# micropeak.net
KiCad netlist of a schematic drawn in EAGLE
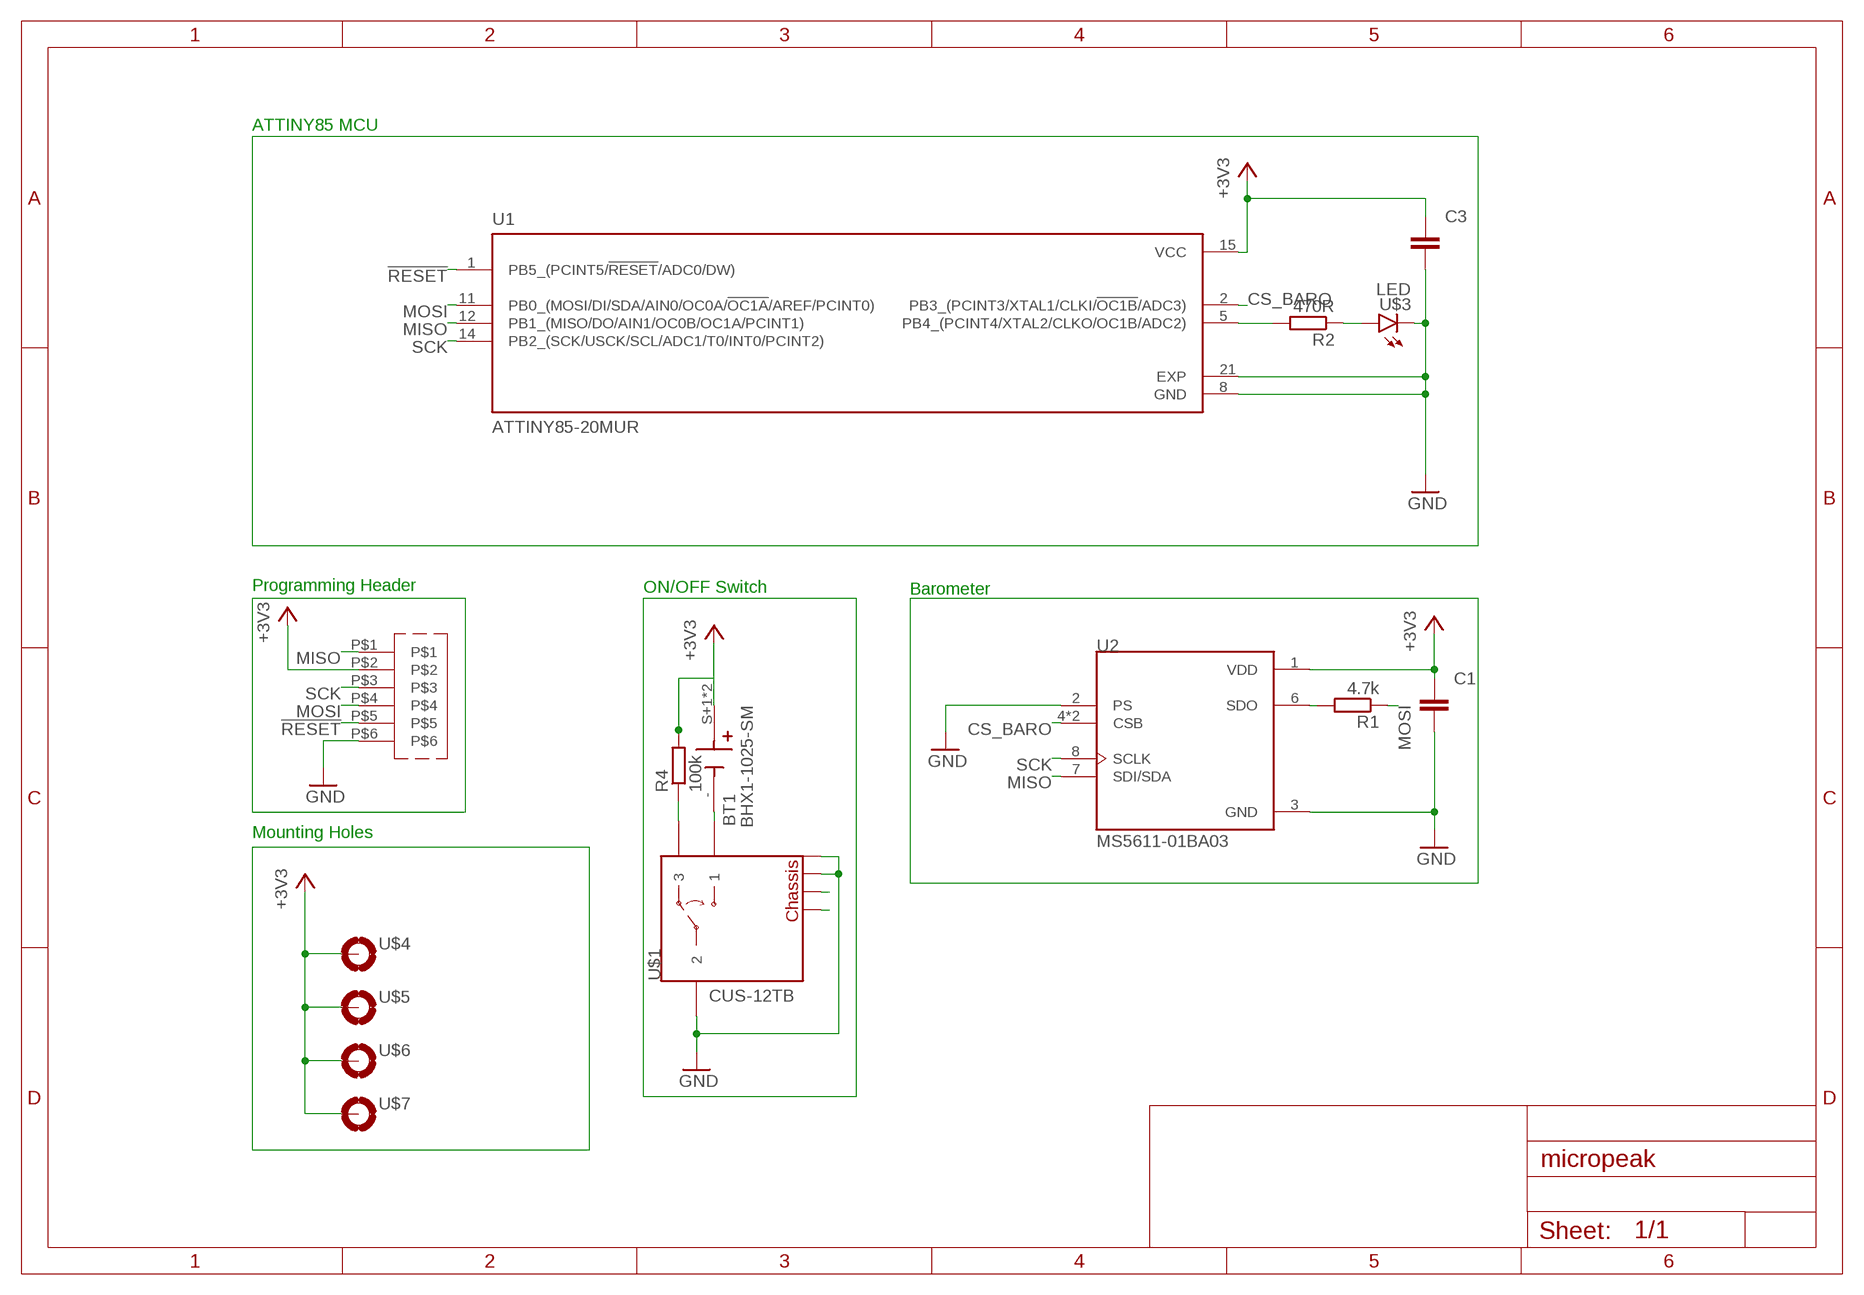
[diagram p0: schematic, sheet 1]

(export (version "E")
  (design (tool "Eeschema 10.0.6"))
  (components
    (comp (ref "BT1")
      (value "BHX1-1025-SM")
      (footprint "eagle-import:BAT_BHX1-1025-SM")
      (fields (field (name "MF") "MPD (Memory Protection Devices)"))
      (libsource (lib "eagle-import") (part "BHX1-1025-SM"))
    )
    (comp (ref "C1")
      (value "C-EUC0402")
      (footprint "eagle-import:C0402")
      (libsource (lib "eagle-import") (part "C-EUC0402"))
    )
    (comp (ref "C3")
      (value "C-EUC0402")
      (footprint "eagle-import:C0402")
      (libsource (lib "eagle-import") (part "C-EUC0402"))
    )
    (comp (ref "R1")
      (value "4.7k")
      (footprint "eagle-import:R0402")
      (libsource (lib "eagle-import") (part "R-EU_R0402"))
    )
    (comp (ref "R2")
      (value "470R")
      (footprint "eagle-import:R0402")
      (libsource (lib "eagle-import") (part "R-EU_R0402"))
    )
    (comp (ref "R4")
      (value "100k")
      (footprint "eagle-import:R0402")
      (libsource (lib "eagle-import") (part "R-EU_R0402"))
    )
    (comp (ref "U$1")
      (value "CUS-12TB")
      (footprint "eagle-import:CUS-12B")
      (fields (field (name "MF") "Nidec Copal"))
      (libsource (lib "eagle-import") (part "CUS-12TB"))
    )
    (comp (ref "U$2")
      (value "1X6_PROG_HEADER")
      (footprint "eagle-import:1X6_SMD_HEADER_PADS")
      (libsource (lib "eagle-import") (part "1X6_PROG_HEADER"))
    )
    (comp (ref "U$3")
      (value "LED")
      (footprint "eagle-import:LED_LYT68B-T2V1-26-Z")
      (libsource (lib "eagle-import") (part "LED"))
    )
    (comp (ref "U$4")
      (value "MOUNT_HOLE")
      (footprint "eagle-import:2,8-PAD")
      (libsource (lib "eagle-import") (part "MOUNT_HOLE"))
    )
    (comp (ref "U$5")
      (value "MOUNT_HOLE")
      (footprint "eagle-import:2,8-PAD")
      (libsource (lib "eagle-import") (part "MOUNT_HOLE"))
    )
    (comp (ref "U$6")
      (value "MOUNT_HOLE")
      (footprint "eagle-import:2,8-PAD")
      (libsource (lib "eagle-import") (part "MOUNT_HOLE"))
    )
    (comp (ref "U$7")
      (value "MOUNT_HOLE")
      (footprint "eagle-import:2,8-PAD")
      (libsource (lib "eagle-import") (part "MOUNT_HOLE"))
    )
    (comp (ref "U1")
      (value "ATTINY85-20MUR")
      (footprint "eagle-import:QFN50P400X400X80-21N")
      (fields (field (name "MF") "Microchip Technology"))
      (libsource (lib "eagle-import") (part "ATTINY85-20MUR"))
    )
    (comp (ref "U2")
      (value "MS5611-01BA03")
      (footprint "eagle-import:SON125P500X300X100-8N")
      (fields (field (name "COMMENT") "CAT-BLPS0036") (field (name "MF") "TE Connectivity"))
      (libsource (lib "eagle-import") (part "MS5611-01BA03"))
    )
  )
  (nets
    (net (code "1") (name "+3V3") (class "Default")
      (node (ref "BT1") (pin "S+1") (pinfunction "+_S+1") (pintype "passive"))
      (node (ref "BT1") (pin "S+2") (pinfunction "+_S+2") (pintype "passive"))
      (node (ref "C1") (pin "1") (pinfunction "1_1") (pintype "passive"))
      (node (ref "C3") (pin "1") (pinfunction "1_1") (pintype "passive"))
      (node (ref "R4") (pin "2") (pinfunction "2_2") (pintype "passive"))
      (node (ref "U$2") (pin "P$2") (pinfunction "P$2_P$2") (pintype "bidirectional"))
      (node (ref "U$4") (pin "B2,8") (pinfunction "MOUNT_B2,8") (pintype "passive"))
      (node (ref "U$5") (pin "B2,8") (pinfunction "MOUNT_B2,8") (pintype "passive"))
      (node (ref "U$6") (pin "B2,8") (pinfunction "MOUNT_B2,8") (pintype "passive"))
      (node (ref "U$7") (pin "B2,8") (pinfunction "MOUNT_B2,8") (pintype "passive"))
      (node (ref "U1") (pin "15") (pinfunction "VCC_15") (pintype "power_in"))
      (node (ref "U2") (pin "1") (pinfunction "VDD_1") (pintype "power_in"))
    )
    (net (code "2") (name "/CS_BARO") (class "Default")
      (node (ref "U1") (pin "2") (pinfunction "PB3_(PCINT3/XTAL1/CLKI/~{OC1B}/ADC3)_2") (pintype "bidirectional"))
      (node (ref "U2") (pin "4") (pinfunction "CSB_4") (pintype "input"))
      (node (ref "U2") (pin "5") (pinfunction "CSB_5") (pintype "input"))
    )
    (net (code "3") (name "/MISO") (class "Default")
      (node (ref "U$2") (pin "P$1") (pinfunction "P$1_P$1") (pintype "bidirectional"))
      (node (ref "U1") (pin "12") (pinfunction "PB1_(MISO/DO/AIN1/OC0B/OC1A/PCINT1)_12") (pintype "bidirectional"))
      (node (ref "U2") (pin "7") (pinfunction "SDI/SDA_7") (pintype "bidirectional"))
    )
    (net (code "4") (name "/MOSI") (class "Default")
      (node (ref "R1") (pin "1") (pinfunction "1_1") (pintype "passive"))
      (node (ref "U$2") (pin "P$4") (pinfunction "P$4_P$4") (pintype "bidirectional"))
      (node (ref "U1") (pin "11") (pinfunction "PB0_(MOSI/DI/SDA/AIN0/OC0A/~{OC1A}/AREF/PCINT0)_11") (pintype "bidirectional"))
    )
    (net (code "5") (name "/SCK") (class "Default")
      (node (ref "U$2") (pin "P$3") (pinfunction "P$3_P$3") (pintype "bidirectional"))
      (node (ref "U1") (pin "14") (pinfunction "PB2_(SCK/USCK/SCL/ADC1/T0/INT0/PCINT2)_14") (pintype "bidirectional"))
      (node (ref "U2") (pin "8") (pinfunction "SCLK_8") (pintype "input"))
    )
    (net (code "6") (name "/~{RESET}") (class "Default")
      (node (ref "U$2") (pin "P$5") (pinfunction "P$5_P$5") (pintype "bidirectional"))
      (node (ref "U1") (pin "1") (pinfunction "PB5_(PCINT5/~{RESET}/ADC0/DW)_1") (pintype "bidirectional"))
    )
    (net (code "7") (name "GND") (class "Default")
      (node (ref "C1") (pin "2") (pinfunction "2_2") (pintype "passive"))
      (node (ref "C3") (pin "2") (pinfunction "2_2") (pintype "passive"))
      (node (ref "U$1") (pin "P$2") (pinfunction "2_P$2") (pintype "bidirectional"))
      (node (ref "U$1") (pin "P$4") (pinfunction "GND_P$4") (pintype "power_in"))
      (node (ref "U$1") (pin "P$5") (pinfunction "GND_P$5") (pintype "power_in"))
      (node (ref "U$2") (pin "P$6") (pinfunction "P$6_P$6") (pintype "bidirectional"))
      (node (ref "U$3") (pin "C") (pinfunction "C_C") (pintype "passive"))
      (node (ref "U1") (pin "21") (pinfunction "EXP_21") (pintype "power_in"))
      (node (ref "U1") (pin "8") (pinfunction "GND_8") (pintype "power_in"))
      (node (ref "U2") (pin "2") (pinfunction "PS_2") (pintype "input"))
      (node (ref "U2") (pin "3") (pinfunction "GND_3") (pintype "power_in"))
    )
    (net (code "8") (name "Net-(R2-Pad1)") (class "Default")
      (node (ref "R2") (pin "1") (pinfunction "1_1") (pintype "passive"))
      (node (ref "U$3") (pin "A") (pinfunction "A_A") (pintype "passive"))
    )
    (net (code "9") (name "Net-(U$1-1)") (class "Default")
      (node (ref "BT1") (pin "-") (pinfunction "-_-") (pintype "passive"))
      (node (ref "U$1") (pin "P$1") (pinfunction "1_P$1") (pintype "bidirectional"))
    )
    (net (code "10") (name "Net-(U$1-3)") (class "Default")
      (node (ref "R4") (pin "1") (pinfunction "1_1") (pintype "passive"))
      (node (ref "U$1") (pin "P$3") (pinfunction "3_P$3") (pintype "bidirectional"))
    )
    (net (code "11") (name "Net-(U1-PB4_(PCINT4{slash}XTAL2{slash}CLKO{slash}OC1B{slash}ADC2))") (class "Default")
      (node (ref "R2") (pin "2") (pinfunction "2_2") (pintype "passive"))
      (node (ref "U1") (pin "5") (pinfunction "PB4_(PCINT4/XTAL2/CLKO/OC1B/ADC2)_5") (pintype "bidirectional"))
    )
    (net (code "12") (name "Net-(U2-SDO)") (class "Default")
      (node (ref "R1") (pin "2") (pinfunction "2_2") (pintype "passive"))
      (node (ref "U2") (pin "6") (pinfunction "SDO_6") (pintype "output"))
    )
    (net (code "13") (name "unconnected-(U$1-GND-PadP$6)") (class "Default")
      (node (ref "U$1") (pin "P$6") (pinfunction "GND_P$6") (pintype "power_in"))
    )
    (net (code "14") (name "unconnected-(U$1-GND-PadP$7)") (class "Default")
      (node (ref "U$1") (pin "P$7") (pinfunction "GND_P$7") (pintype "power_in"))
    )
  )
)
